# maintemp_revised_edition_2_20_18.net
KiCad netlist of a schematic drawn in EAGLE
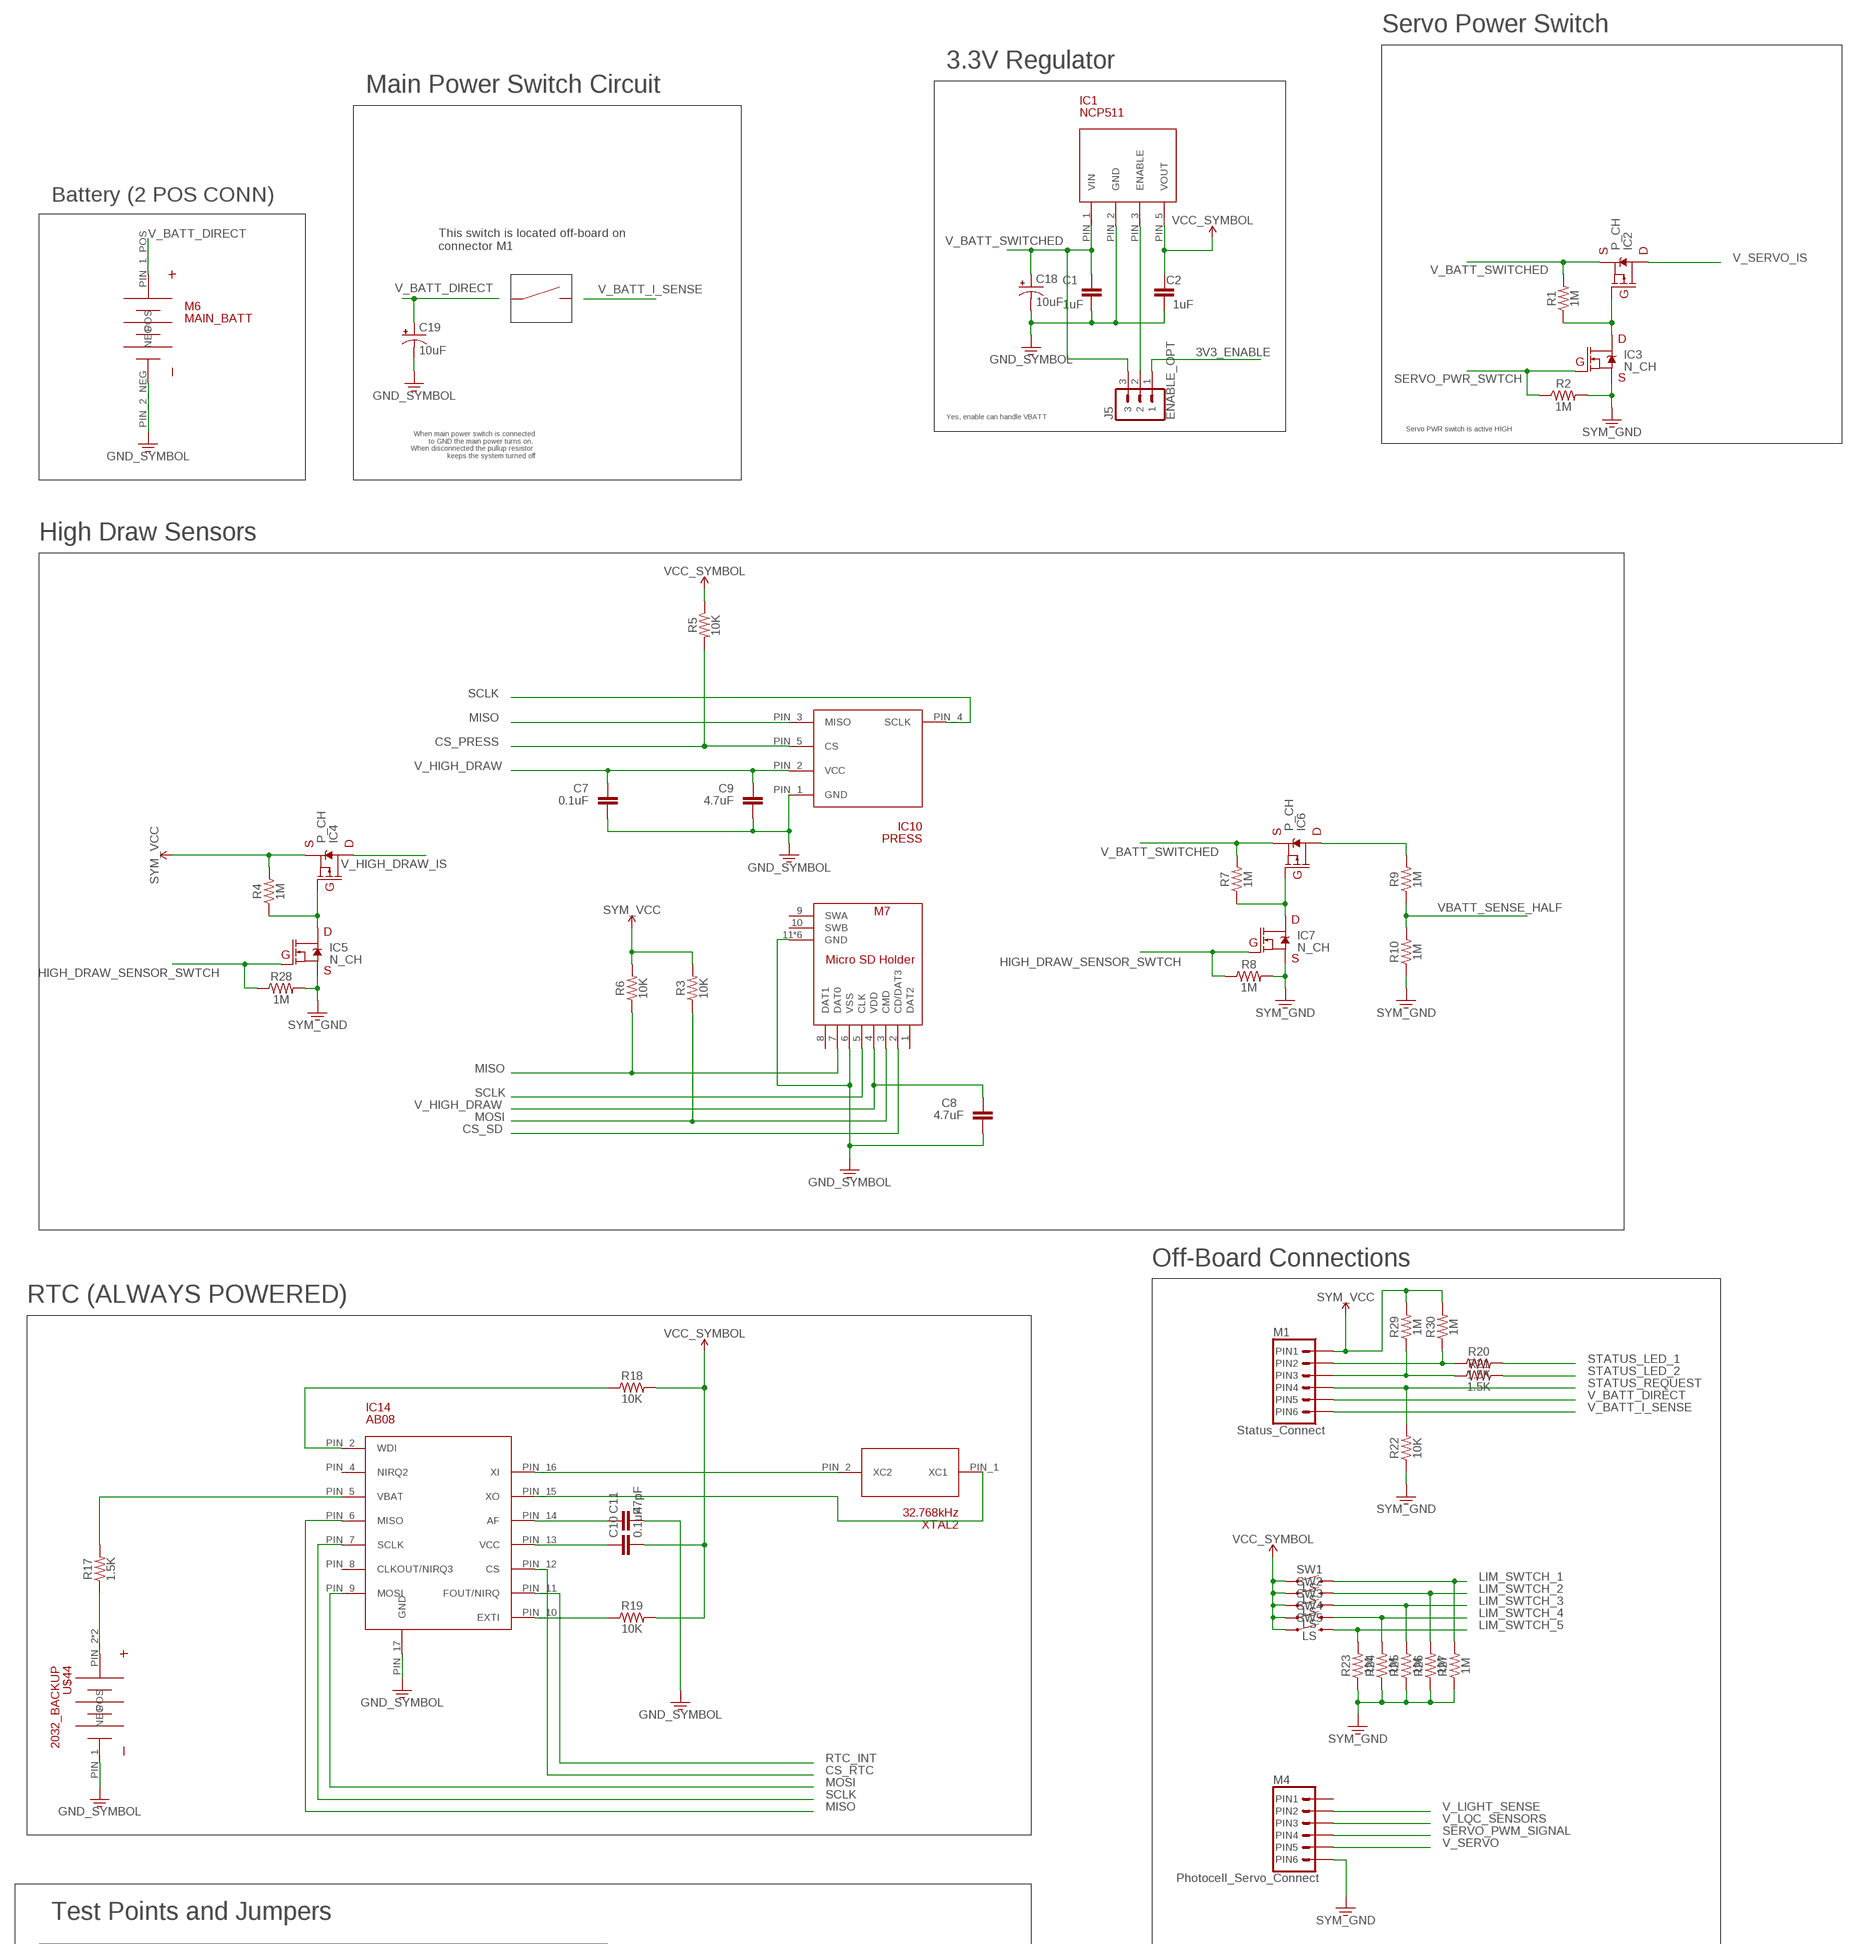
[diagram p0: schematic, sheet 1, part 1 of 3]
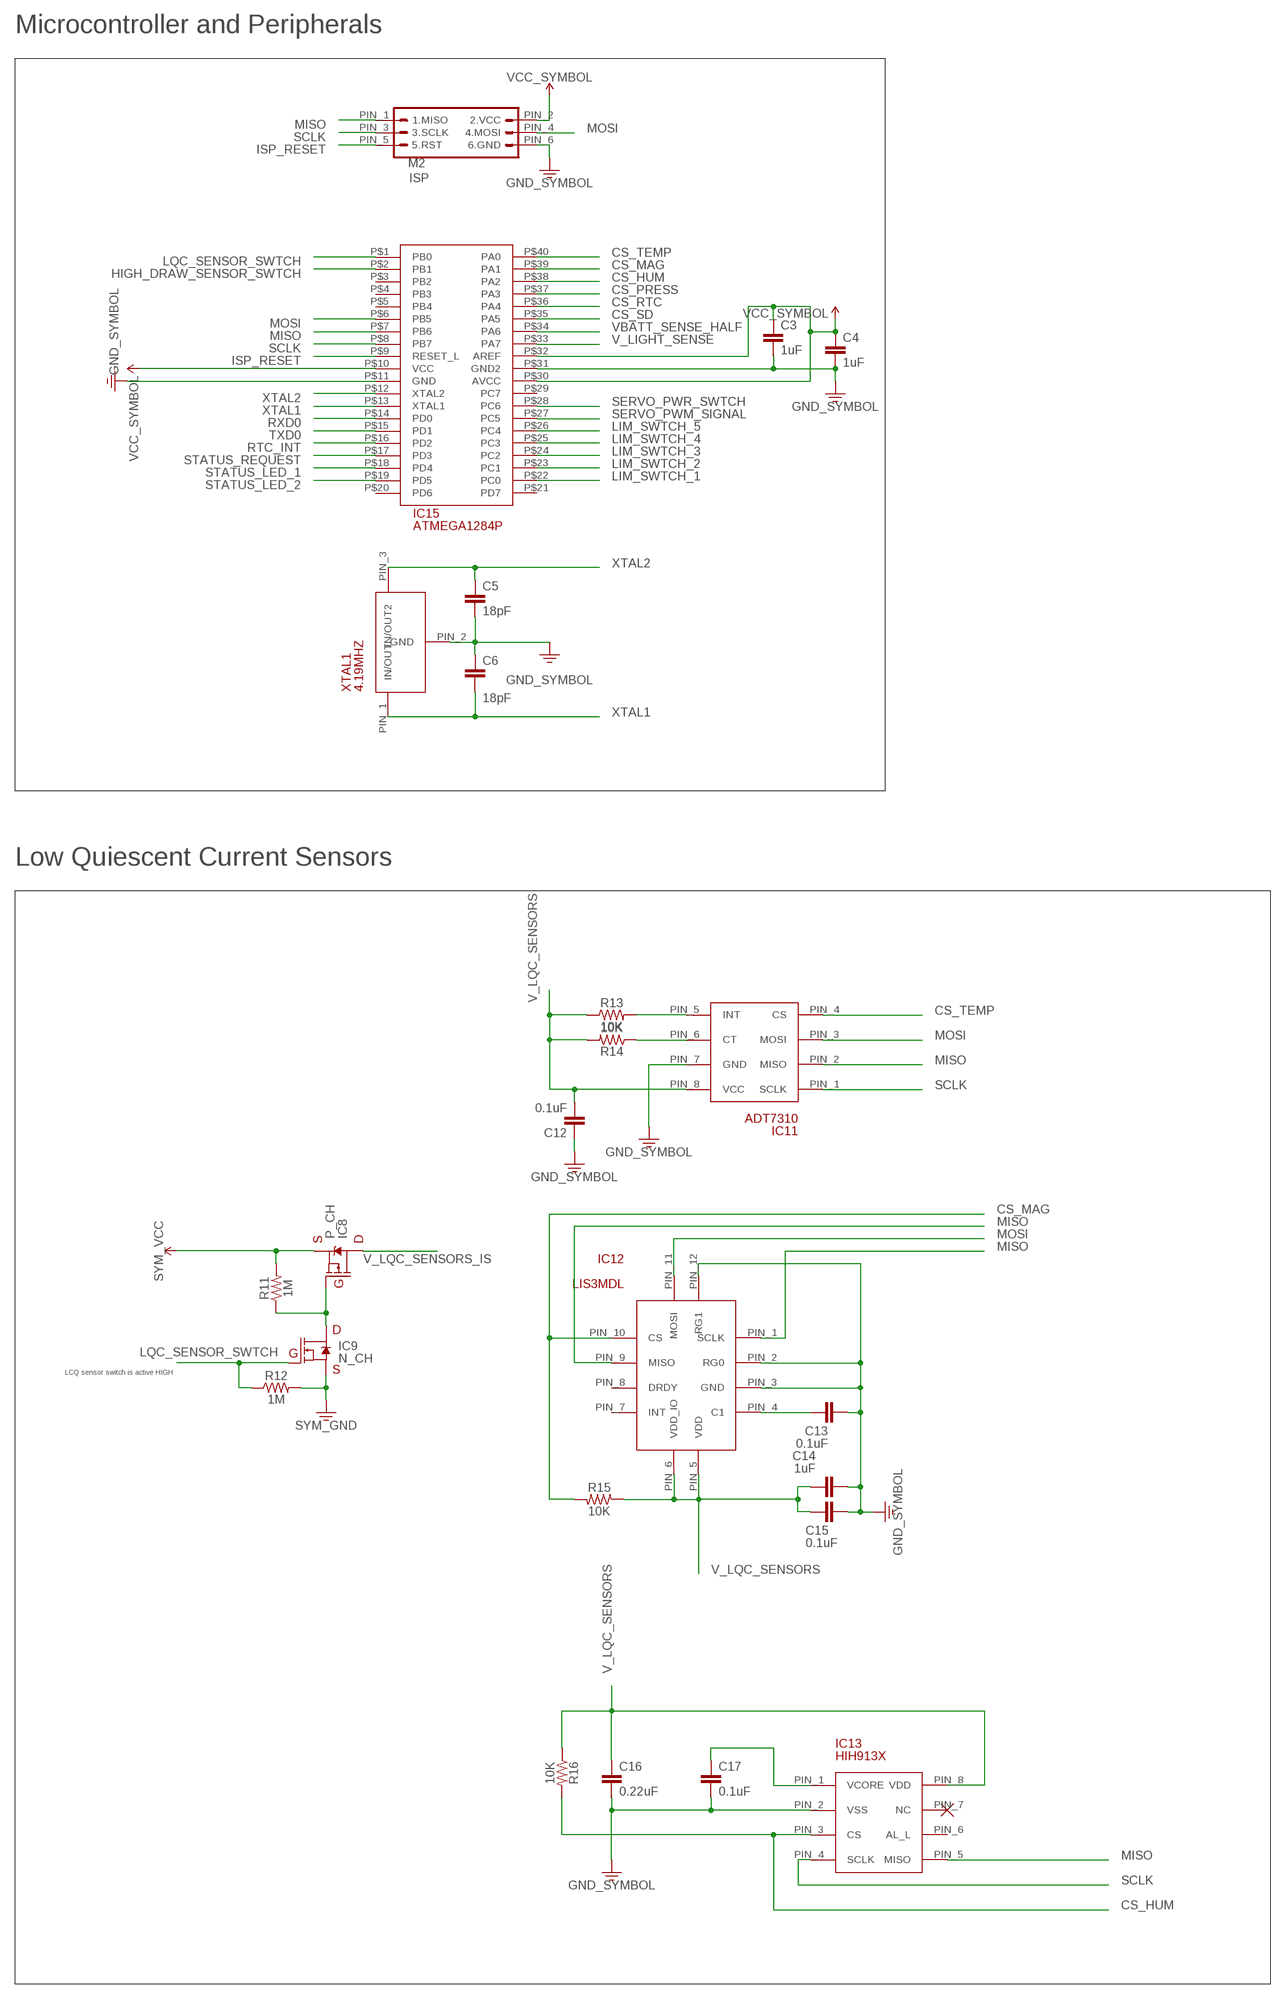
[diagram p1: schematic, sheet 1, part 2 of 3]
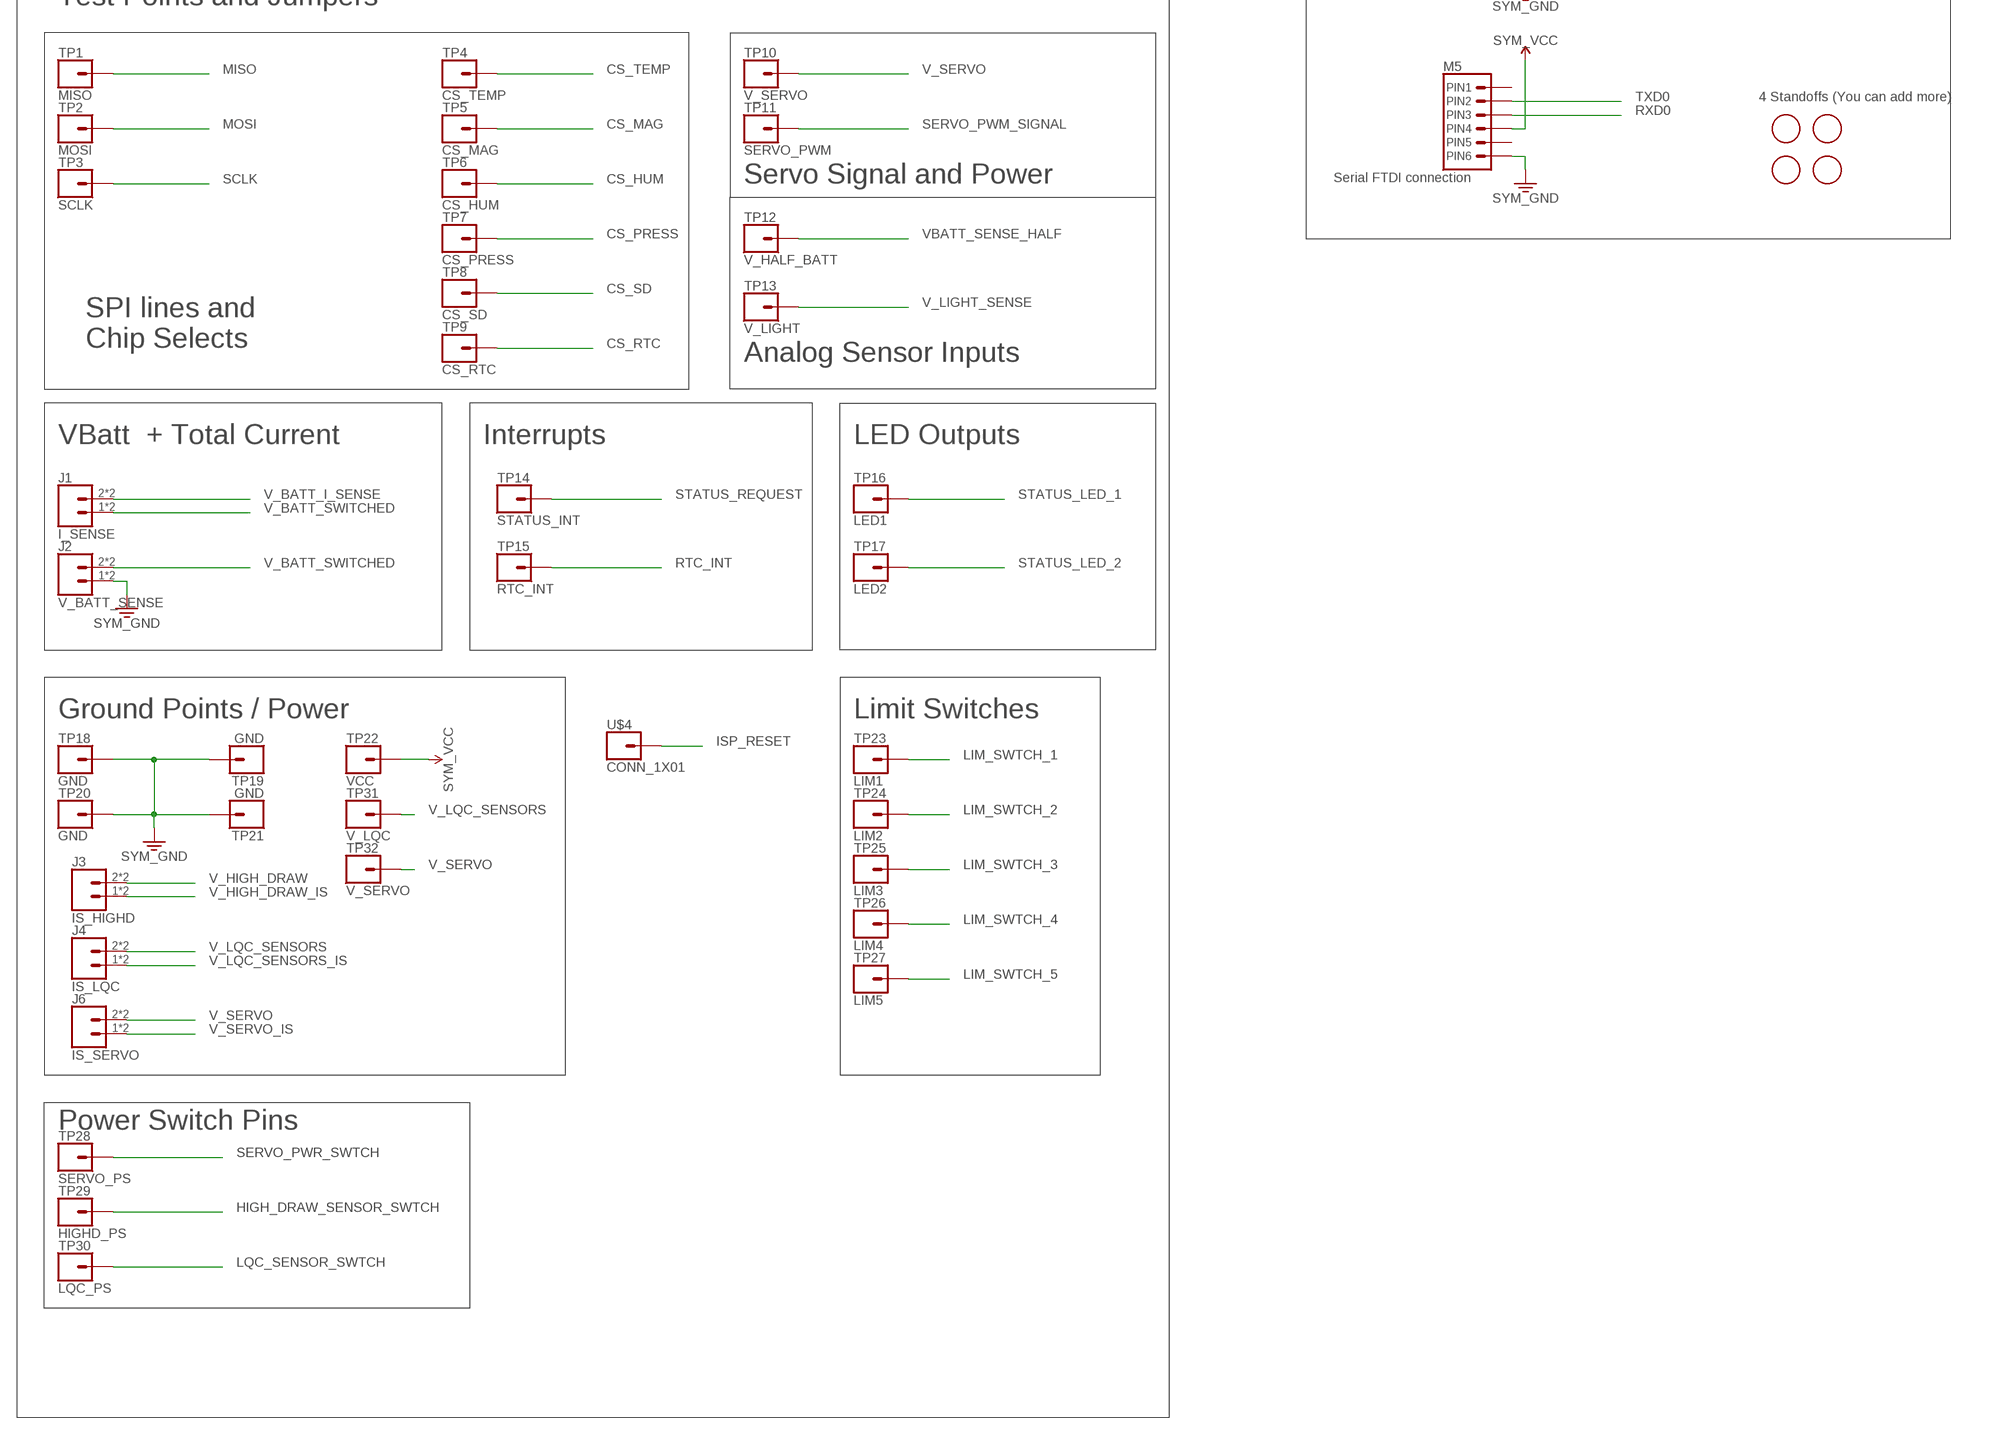
[diagram p2: schematic, sheet 1, part 3 of 3]

(export (version "E")
  (design (tool "Eeschema 10.0.6"))
  (components
    (comp (ref "C1")
      (value "1uF")
      (footprint "eagle-import:SMD_0603")
      (libsource (lib "eagle-import") (part "CAP_1UF"))
    )
    (comp (ref "C2")
      (value "1uF")
      (footprint "eagle-import:SMD_0603")
      (libsource (lib "eagle-import") (part "CAP_1UF"))
    )
    (comp (ref "C3")
      (value "1uF")
      (footprint "eagle-import:SMD_0603")
      (libsource (lib "eagle-import") (part "CAP_1UF"))
    )
    (comp (ref "C4")
      (value "1uF")
      (footprint "eagle-import:SMD_0603")
      (libsource (lib "eagle-import") (part "CAP_1UF"))
    )
    (comp (ref "C5")
      (value "18pF")
      (footprint "eagle-import:SMD_0603")
      (libsource (lib "eagle-import") (part "CAP_18PF"))
    )
    (comp (ref "C6")
      (value "18pF")
      (footprint "eagle-import:SMD_0603")
      (libsource (lib "eagle-import") (part "CAP_18PF"))
    )
    (comp (ref "C7")
      (value "0.1uF")
      (footprint "eagle-import:SMD_0603")
      (libsource (lib "eagle-import") (part "CAP_0.1UF"))
    )
    (comp (ref "C8")
      (value "4.7uF")
      (footprint "eagle-import:SMD_0603")
      (libsource (lib "eagle-import") (part "CAP_4.7UF"))
    )
    (comp (ref "C9")
      (value "4.7uF")
      (footprint "eagle-import:SMD_0603")
      (libsource (lib "eagle-import") (part "CAP_4.7UF"))
    )
    (comp (ref "C10")
      (value "0.1uF")
      (footprint "eagle-import:0603")
      (libsource (lib "eagle-import") (part "0.1UF_CAP"))
    )
    (comp (ref "C11")
      (value "47pF")
      (footprint "eagle-import:0603")
      (libsource (lib "eagle-import") (part "47PF_CAP"))
    )
    (comp (ref "C12")
      (value "0.1uF")
      (footprint "eagle-import:SMD_0603")
      (libsource (lib "eagle-import") (part "CAP_0.1UF"))
    )
    (comp (ref "C13")
      (value "0.1uF")
      (footprint "eagle-import:SMD_0603")
      (libsource (lib "eagle-import") (part "CAP_0.1UF"))
    )
    (comp (ref "C14")
      (value "1uF")
      (footprint "eagle-import:SMD_0603")
      (libsource (lib "eagle-import") (part "CAP_1UF"))
    )
    (comp (ref "C15")
      (value "0.1uF")
      (footprint "eagle-import:SMD_0603")
      (libsource (lib "eagle-import") (part "CAP_0.1UF"))
    )
    (comp (ref "C16")
      (value "0.22uF")
      (footprint "eagle-import:SMD_0603")
      (libsource (lib "eagle-import") (part "CAP_0.22UF"))
    )
    (comp (ref "C17")
      (value "0.1uF")
      (footprint "eagle-import:SMD_0603")
      (libsource (lib "eagle-import") (part "CAP_0.1UF"))
    )
    (comp (ref "C18")
      (value "10uF")
      (footprint "eagle-import:CAP-PTH-2.54")
      (libsource (lib "eagle-import") (part "CAP_ELECTRO"))
    )
    (comp (ref "C19")
      (value "10uF")
      (footprint "eagle-import:CAP-PTH-2.54")
      (libsource (lib "eagle-import") (part "CAP_ELECTRO"))
    )
    (comp (ref "IC1")
      (value "NCP511")
      (footprint "eagle-import:TSOP-5")
      (libsource (lib "eagle-import") (part "REG_NCP511"))
    )
    (comp (ref "IC2")
      (value "P_CH")
      (footprint "eagle-import:SOT23")
      (libsource (lib "eagle-import") (part "ZMISC_MOSFET_P_CHANNEL"))
    )
    (comp (ref "IC3")
      (value "N_CH")
      (footprint "eagle-import:SOT23")
      (libsource (lib "eagle-import") (part "ZMISC_MOSFET_N_CHANNEL"))
    )
    (comp (ref "IC4")
      (value "P_CH")
      (footprint "eagle-import:SOT23")
      (libsource (lib "eagle-import") (part "ZMISC_MOSFET_P_CHANNEL"))
    )
    (comp (ref "IC5")
      (value "N_CH")
      (footprint "eagle-import:SOT23")
      (libsource (lib "eagle-import") (part "ZMISC_MOSFET_N_CHANNEL"))
    )
    (comp (ref "IC6")
      (value "P_CH")
      (footprint "eagle-import:SOT23")
      (libsource (lib "eagle-import") (part "ZMISC_MOSFET_P_CHANNEL"))
    )
    (comp (ref "IC7")
      (value "N_CH")
      (footprint "eagle-import:SOT23")
      (libsource (lib "eagle-import") (part "ZMISC_MOSFET_N_CHANNEL"))
    )
    (comp (ref "IC8")
      (value "P_CH")
      (footprint "eagle-import:SOT23")
      (libsource (lib "eagle-import") (part "ZMISC_MOSFET_P_CHANNEL"))
    )
    (comp (ref "IC9")
      (value "N_CH")
      (footprint "eagle-import:SOT23")
      (libsource (lib "eagle-import") (part "ZMISC_MOSFET_N_CHANNEL"))
    )
    (comp (ref "IC10")
      (value "PRESS")
      (footprint "eagle-import:8-DIP")
      (libsource (lib "eagle-import") (part "SENS_PRESS_RSC"))
    )
    (comp (ref "IC11")
      (value "ADT7310")
      (footprint "eagle-import:SOIC-8")
      (libsource (lib "eagle-import") (part "TEMP_ADT7310"))
    )
    (comp (ref "IC12")
      (value "LIS3MDL")
      (footprint "eagle-import:LGA-12")
      (libsource (lib "eagle-import") (part "MAG_LIS3MDL"))
    )
    (comp (ref "IC13")
      (value "HIH913X")
      (footprint "eagle-import:SOIC-8")
      (libsource (lib "eagle-import") (part "HUM_HIH913X"))
    )
    (comp (ref "IC14")
      (value "AB08")
      (footprint "eagle-import:QFN16_3X3")
      (libsource (lib "eagle-import") (part "RTC_AB08"))
    )
    (comp (ref "IC15")
      (value "ATMEGA1284P")
      (footprint "eagle-import:40-DIP")
      (libsource (lib "eagle-import") (part "UC_ATMEGA1284P"))
    )
    (comp (ref "J1")
      (value "I_SENSE")
      (footprint "eagle-import:1X02")
      (libsource (lib "eagle-import") (part "ZMISC_JUMPER"))
    )
    (comp (ref "J2")
      (value "V_BATT_SENSE")
      (footprint "eagle-import:1X02")
      (libsource (lib "eagle-import") (part "ZMISC_JUMPER"))
    )
    (comp (ref "J3")
      (value "IS_HIGHD")
      (footprint "eagle-import:1X02")
      (libsource (lib "eagle-import") (part "ZMISC_JUMPER"))
    )
    (comp (ref "J4")
      (value "IS_LQC")
      (footprint "eagle-import:1X02")
      (libsource (lib "eagle-import") (part "ZMISC_JUMPER"))
    )
    (comp (ref "J5")
      (value "ENABLE_OPT")
      (footprint "eagle-import:1X03")
      (libsource (lib "eagle-import") (part "CONN_1X03"))
    )
    (comp (ref "J6")
      (value "IS_SERVO")
      (footprint "eagle-import:1X02")
      (libsource (lib "eagle-import") (part "ZMISC_JUMPER"))
    )
    (comp (ref "M1")
      (value "Status_Connect")
      (footprint "eagle-import:1X06")
      (libsource (lib "eagle-import") (part "CONN_SERIAL"))
    )
    (comp (ref "M2")
      (value "ISP")
      (footprint "eagle-import:2X3")
      (libsource (lib "eagle-import") (part "CONN_ISP"))
    )
    (comp (ref "M4")
      (value "Photocell_Servo_Connect")
      (footprint "eagle-import:1X06")
      (libsource (lib "eagle-import") (part "CONN_SERIAL"))
    )
    (comp (ref "M5")
      (value "Serial FTDI connection")
      (footprint "eagle-import:1X06")
      (libsource (lib "eagle-import") (part "CONN_SERIAL"))
    )
    (comp (ref "M6")
      (value "MAIN_BATT")
      (footprint "eagle-import:1-1318300-2")
      (libsource (lib "eagle-import") (part "PWR_MAIN_BATT"))
    )
    (comp (ref "M7")
      (value "SD")
      (footprint "eagle-import:MICRO-SD")
      (libsource (lib "eagle-import") (part "SENS_MICRO-SD"))
    )
    (comp (ref "R1")
      (value "1M")
      (footprint "eagle-import:SMD_0603")
      (libsource (lib "eagle-import") (part "RES_10K"))
    )
    (comp (ref "R2")
      (value "1M")
      (footprint "eagle-import:SMD_0603")
      (libsource (lib "eagle-import") (part "RES_10K"))
    )
    (comp (ref "R3")
      (value "10K")
      (footprint "eagle-import:SMD_0603")
      (libsource (lib "eagle-import") (part "RES_10K"))
    )
    (comp (ref "R4")
      (value "1M")
      (footprint "eagle-import:SMD_0603")
      (libsource (lib "eagle-import") (part "RES_10K"))
    )
    (comp (ref "R5")
      (value "10K")
      (footprint "eagle-import:SMD_0603")
      (libsource (lib "eagle-import") (part "RES_10K"))
    )
    (comp (ref "R6")
      (value "10K")
      (footprint "eagle-import:SMD_0603")
      (libsource (lib "eagle-import") (part "RES_10K"))
    )
    (comp (ref "R7")
      (value "1M")
      (footprint "eagle-import:SMD_0603")
      (libsource (lib "eagle-import") (part "RES_10K"))
    )
    (comp (ref "R8")
      (value "1M")
      (footprint "eagle-import:SMD_0603")
      (libsource (lib "eagle-import") (part "RES_10K"))
    )
    (comp (ref "R9")
      (value "1M")
      (footprint "eagle-import:SMD_0603")
      (libsource (lib "eagle-import") (part "RES_1M"))
    )
    (comp (ref "R10")
      (value "1M")
      (footprint "eagle-import:SMD_0603")
      (libsource (lib "eagle-import") (part "RES_1M"))
    )
    (comp (ref "R11")
      (value "1M")
      (footprint "eagle-import:SMD_0603")
      (libsource (lib "eagle-import") (part "RES_10K"))
    )
    (comp (ref "R12")
      (value "1M")
      (footprint "eagle-import:SMD_0603")
      (libsource (lib "eagle-import") (part "RES_10K"))
    )
    (comp (ref "R13")
      (value "10K")
      (footprint "eagle-import:SMD_0603")
      (libsource (lib "eagle-import") (part "RES_10K"))
    )
    (comp (ref "R14")
      (value "10K")
      (footprint "eagle-import:SMD_0603")
      (libsource (lib "eagle-import") (part "RES_10K"))
    )
    (comp (ref "R15")
      (value "10K")
      (footprint "eagle-import:SMD_0603")
      (libsource (lib "eagle-import") (part "RES_10K"))
    )
    (comp (ref "R16")
      (value "10K")
      (footprint "eagle-import:SMD_0603")
      (libsource (lib "eagle-import") (part "RES_10K"))
    )
    (comp (ref "R17")
      (value "1.5K")
      (footprint "eagle-import:0603")
      (libsource (lib "eagle-import") (part "1.5K_RES"))
    )
    (comp (ref "R18")
      (value "10K")
      (footprint "eagle-import:0603")
      (libsource (lib "eagle-import") (part "10K_RES"))
    )
    (comp (ref "R19")
      (value "10K")
      (footprint "eagle-import:0603")
      (libsource (lib "eagle-import") (part "10K_RES"))
    )
    (comp (ref "R20")
      (value "1.5K")
      (footprint "eagle-import:SMD_0603")
      (libsource (lib "eagle-import") (part "RES_1.5K"))
    )
    (comp (ref "R21")
      (value "1.5K")
      (footprint "eagle-import:SMD_0603")
      (libsource (lib "eagle-import") (part "RES_1.5K"))
    )
    (comp (ref "R22")
      (value "10K")
      (footprint "eagle-import:SMD_0603")
      (libsource (lib "eagle-import") (part "RES_10K"))
    )
    (comp (ref "R23")
      (value "1M")
      (footprint "eagle-import:SMD_0603")
      (libsource (lib "eagle-import") (part "RES_1M"))
    )
    (comp (ref "R24")
      (value "1M")
      (footprint "eagle-import:SMD_0603")
      (libsource (lib "eagle-import") (part "RES_1M"))
    )
    (comp (ref "R25")
      (value "1M")
      (footprint "eagle-import:SMD_0603")
      (libsource (lib "eagle-import") (part "RES_1M"))
    )
    (comp (ref "R26")
      (value "1M")
      (footprint "eagle-import:SMD_0603")
      (libsource (lib "eagle-import") (part "RES_1M"))
    )
    (comp (ref "R27")
      (value "1M")
      (footprint "eagle-import:SMD_0603")
      (libsource (lib "eagle-import") (part "RES_1M"))
    )
    (comp (ref "R28")
      (value "1M")
      (footprint "eagle-import:SMD_0603")
      (libsource (lib "eagle-import") (part "RES_10K"))
    )
    (comp (ref "R29")
      (value "1M")
      (footprint "eagle-import:SMD_0603")
      (libsource (lib "eagle-import") (part "RES_1M"))
    )
    (comp (ref "R30")
      (value "1M")
      (footprint "eagle-import:SMD_0603")
      (libsource (lib "eagle-import") (part "RES_1M"))
    )
    (comp (ref "SW1")
      (value "LS")
      (footprint "eagle-import:SNAPSWITCH")
      (libsource (lib "eagle-import") (part "LIMITSWITCHBASE"))
    )
    (comp (ref "SW2")
      (value "LS")
      (footprint "eagle-import:SNAPSWITCH")
      (libsource (lib "eagle-import") (part "LIMITSWITCHBASE"))
    )
    (comp (ref "SW3")
      (value "LS")
      (footprint "eagle-import:SNAPSWITCH")
      (libsource (lib "eagle-import") (part "LIMITSWITCHBASE"))
    )
    (comp (ref "SW4")
      (value "LS")
      (footprint "eagle-import:SNAPSWITCH")
      (libsource (lib "eagle-import") (part "LIMITSWITCHBASE"))
    )
    (comp (ref "SW5")
      (value "LS")
      (footprint "eagle-import:SNAPSWITCH")
      (libsource (lib "eagle-import") (part "LIMITSWITCHBASE"))
    )
    (comp (ref "TP1")
      (value "MISO")
      (footprint "eagle-import:1X01")
      (libsource (lib "eagle-import") (part "CONN_1X01"))
    )
    (comp (ref "TP2")
      (value "MOSI")
      (footprint "eagle-import:1X01")
      (libsource (lib "eagle-import") (part "CONN_1X01"))
    )
    (comp (ref "TP3")
      (value "SCLK")
      (footprint "eagle-import:1X01")
      (libsource (lib "eagle-import") (part "CONN_1X01"))
    )
    (comp (ref "TP4")
      (value "CS_TEMP")
      (footprint "eagle-import:1X01")
      (libsource (lib "eagle-import") (part "CONN_1X01"))
    )
    (comp (ref "TP5")
      (value "CS_MAG")
      (footprint "eagle-import:1X01")
      (libsource (lib "eagle-import") (part "CONN_1X01"))
    )
    (comp (ref "TP6")
      (value "CS_HUM")
      (footprint "eagle-import:1X01")
      (libsource (lib "eagle-import") (part "CONN_1X01"))
    )
    (comp (ref "TP7")
      (value "CS_PRESS")
      (footprint "eagle-import:1X01")
      (libsource (lib "eagle-import") (part "CONN_1X01"))
    )
    (comp (ref "TP8")
      (value "CS_SD")
      (footprint "eagle-import:1X01")
      (libsource (lib "eagle-import") (part "CONN_1X01"))
    )
    (comp (ref "TP9")
      (value "CS_RTC")
      (footprint "eagle-import:1X01")
      (libsource (lib "eagle-import") (part "CONN_1X01"))
    )
    (comp (ref "TP10")
      (value "V_SERVO")
      (footprint "eagle-import:1X01")
      (libsource (lib "eagle-import") (part "CONN_1X01"))
    )
    (comp (ref "TP11")
      (value "SERVO_PWM")
      (footprint "eagle-import:1X01")
      (libsource (lib "eagle-import") (part "CONN_1X01"))
    )
    (comp (ref "TP12")
      (value "V_HALF_BATT")
      (footprint "eagle-import:1X01")
      (libsource (lib "eagle-import") (part "CONN_1X01"))
    )
    (comp (ref "TP13")
      (value "V_LIGHT")
      (footprint "eagle-import:1X01")
      (libsource (lib "eagle-import") (part "CONN_1X01"))
    )
    (comp (ref "TP14")
      (value "STATUS_INT")
      (footprint "eagle-import:1X01")
      (libsource (lib "eagle-import") (part "CONN_1X01"))
    )
    (comp (ref "TP15")
      (value "RTC_INT")
      (footprint "eagle-import:1X01")
      (libsource (lib "eagle-import") (part "CONN_1X01"))
    )
    (comp (ref "TP16")
      (value "LED1")
      (footprint "eagle-import:1X01")
      (libsource (lib "eagle-import") (part "CONN_1X01"))
    )
    (comp (ref "TP17")
      (value "LED2")
      (footprint "eagle-import:1X01")
      (libsource (lib "eagle-import") (part "CONN_1X01"))
    )
    (comp (ref "TP18")
      (value "GND")
      (footprint "eagle-import:1X01")
      (libsource (lib "eagle-import") (part "CONN_1X01"))
    )
    (comp (ref "TP19")
      (value "GND")
      (footprint "eagle-import:1X01")
      (libsource (lib "eagle-import") (part "CONN_1X01"))
    )
    (comp (ref "TP20")
      (value "GND")
      (footprint "eagle-import:1X01")
      (libsource (lib "eagle-import") (part "CONN_1X01"))
    )
    (comp (ref "TP21")
      (value "GND")
      (footprint "eagle-import:1X01")
      (libsource (lib "eagle-import") (part "CONN_1X01"))
    )
    (comp (ref "TP22")
      (value "VCC")
      (footprint "eagle-import:1X01")
      (libsource (lib "eagle-import") (part "CONN_1X01"))
    )
    (comp (ref "TP23")
      (value "LIM1")
      (footprint "eagle-import:1X01")
      (libsource (lib "eagle-import") (part "CONN_1X01"))
    )
    (comp (ref "TP24")
      (value "LIM2")
      (footprint "eagle-import:1X01")
      (libsource (lib "eagle-import") (part "CONN_1X01"))
    )
    (comp (ref "TP25")
      (value "LIM3")
      (footprint "eagle-import:1X01")
      (libsource (lib "eagle-import") (part "CONN_1X01"))
    )
    (comp (ref "TP26")
      (value "LIM4")
      (footprint "eagle-import:1X01")
      (libsource (lib "eagle-import") (part "CONN_1X01"))
    )
    (comp (ref "TP27")
      (value "LIM5")
      (footprint "eagle-import:1X01")
      (libsource (lib "eagle-import") (part "CONN_1X01"))
    )
    (comp (ref "TP28")
      (value "SERVO_PS")
      (footprint "eagle-import:1X01")
      (libsource (lib "eagle-import") (part "CONN_1X01"))
    )
    (comp (ref "TP29")
      (value "HIGHD_PS")
      (footprint "eagle-import:1X01")
      (libsource (lib "eagle-import") (part "CONN_1X01"))
    )
    (comp (ref "TP30")
      (value "LQC_PS")
      (footprint "eagle-import:1X01")
      (libsource (lib "eagle-import") (part "CONN_1X01"))
    )
    (comp (ref "TP31")
      (value "V_LQC")
      (footprint "eagle-import:1X01")
      (libsource (lib "eagle-import") (part "CONN_1X01"))
    )
    (comp (ref "TP32")
      (value "V_SERVO")
      (footprint "eagle-import:1X01")
      (libsource (lib "eagle-import") (part "CONN_1X01"))
    )
    (comp (ref "U$4")
      (value "CONN_1X01")
      (footprint "eagle-import:1X01")
      (libsource (lib "eagle-import") (part "CONN_1X01"))
    )
    (comp (ref "U$7")
      (value "STANDOFF")
      (footprint "eagle-import:STANDOFF")
      (libsource (lib "eagle-import") (part "STANDOFF"))
    )
    (comp (ref "U$11")
      (value "STANDOFF")
      (footprint "eagle-import:STANDOFF")
      (libsource (lib "eagle-import") (part "STANDOFF"))
    )
    (comp (ref "U$13")
      (value "STANDOFF")
      (footprint "eagle-import:STANDOFF")
      (libsource (lib "eagle-import") (part "STANDOFF"))
    )
    (comp (ref "U$17")
      (value "STANDOFF")
      (footprint "eagle-import:STANDOFF")
      (libsource (lib "eagle-import") (part "STANDOFF"))
    )
    (comp (ref "U$44")
      (value "2032_BACKUP")
      (footprint "eagle-import:2032")
      (libsource (lib "eagle-import") (part "2032_BACKUP"))
    )
    (comp (ref "XTAL1")
      (value "4.19MHZ")
      (footprint "eagle-import:AT49")
      (libsource (lib "eagle-import") (part "ZMISC_XC"))
    )
    (comp (ref "XTAL2")
      (value "32.768kHz")
      (footprint "eagle-import:ABS07")
      (libsource (lib "eagle-import") (part "XC_RTC"))
    )
  )
  (nets
    (net (code "1") (name "/3V3_ENABLE") (class "Default")
      (node (ref "J5") (pin "1") (pinfunction "1_1") (pintype "passive"))
    )
    (net (code "2") (name "/CS_HUM") (class "Default")
      (node (ref "IC13") (pin "PIN_3") (pinfunction "CS_PIN_3") (pintype "bidirectional"))
      (node (ref "IC15") (pin "P$38") (pinfunction "PA2_P$38") (pintype "bidirectional"))
      (node (ref "R16") (pin "P$2") (pinfunction "2_P$2") (pintype "passive"))
      (node (ref "TP6") (pin "1") (pinfunction "1_1") (pintype "passive"))
    )
    (net (code "3") (name "/CS_MAG") (class "Default")
      (node (ref "IC12") (pin "PIN_10") (pinfunction "CS_PIN_10") (pintype "bidirectional"))
      (node (ref "IC15") (pin "P$39") (pinfunction "PA1_P$39") (pintype "bidirectional"))
      (node (ref "R15") (pin "P$2") (pinfunction "2_P$2") (pintype "passive"))
      (node (ref "TP5") (pin "1") (pinfunction "1_1") (pintype "passive"))
    )
    (net (code "4") (name "/CS_PRESS") (class "Default")
      (node (ref "IC10") (pin "PIN_5") (pinfunction "CS_PIN_5") (pintype "bidirectional"))
      (node (ref "IC15") (pin "P$37") (pinfunction "PA3_P$37") (pintype "bidirectional"))
      (node (ref "R5") (pin "P$2") (pinfunction "2_P$2") (pintype "passive"))
      (node (ref "TP7") (pin "1") (pinfunction "1_1") (pintype "passive"))
    )
    (net (code "5") (name "/CS_RTC") (class "Default")
      (node (ref "IC14") (pin "PIN_12") (pinfunction "CS_PIN_12") (pintype "bidirectional"))
      (node (ref "IC15") (pin "P$36") (pinfunction "PA4_P$36") (pintype "bidirectional"))
      (node (ref "TP9") (pin "1") (pinfunction "1_1") (pintype "passive"))
    )
    (net (code "6") (name "/CS_SD") (class "Default")
      (node (ref "IC15") (pin "P$35") (pinfunction "PA5_P$35") (pintype "bidirectional"))
      (node (ref "M7") (pin "2") (pinfunction "CD/DAT3_2") (pintype "bidirectional"))
      (node (ref "TP8") (pin "1") (pinfunction "1_1") (pintype "passive"))
    )
    (net (code "7") (name "/CS_TEMP") (class "Default")
      (node (ref "IC11") (pin "PIN_4") (pinfunction "CS_PIN_4") (pintype "bidirectional"))
      (node (ref "IC15") (pin "P$40") (pinfunction "PA0_P$40") (pintype "bidirectional"))
      (node (ref "TP4") (pin "1") (pinfunction "1_1") (pintype "passive"))
    )
    (net (code "8") (name "/HIGH_DRAW_SENSOR_SWTCH") (class "Default")
      (node (ref "IC15") (pin "P$2") (pinfunction "PB1_P$2") (pintype "bidirectional"))
      (node (ref "IC5") (pin "1") (pinfunction "G_1") (pintype "bidirectional"))
      (node (ref "IC7") (pin "1") (pinfunction "G_1") (pintype "bidirectional"))
      (node (ref "R28") (pin "P$1") (pinfunction "1_P$1") (pintype "passive"))
      (node (ref "R8") (pin "P$1") (pinfunction "1_P$1") (pintype "passive"))
      (node (ref "TP29") (pin "1") (pinfunction "1_1") (pintype "passive"))
    )
    (net (code "9") (name "/ISP_RESET") (class "Default")
      (node (ref "IC15") (pin "P$9") (pinfunction "RESET_L_P$9") (pintype "bidirectional"))
      (node (ref "M2") (pin "PIN_5") (pinfunction "5.RST_PIN_5") (pintype "bidirectional"))
      (node (ref "U$4") (pin "1") (pinfunction "1_1") (pintype "passive"))
    )
    (net (code "10") (name "/LIM_SWTCH_1") (class "Default")
      (node (ref "IC15") (pin "P$22") (pinfunction "PC0_P$22") (pintype "bidirectional"))
      (node (ref "R27") (pin "P$2") (pinfunction "2_P$2") (pintype "passive"))
      (node (ref "SW1") (pin "PIN_2") (pinfunction "2_PIN_2") (pintype "passive"))
      (node (ref "TP23") (pin "1") (pinfunction "1_1") (pintype "passive"))
    )
    (net (code "11") (name "/LIM_SWTCH_2") (class "Default")
      (node (ref "IC15") (pin "P$23") (pinfunction "PC1_P$23") (pintype "bidirectional"))
      (node (ref "R26") (pin "P$2") (pinfunction "2_P$2") (pintype "passive"))
      (node (ref "SW2") (pin "PIN_2") (pinfunction "2_PIN_2") (pintype "passive"))
      (node (ref "TP24") (pin "1") (pinfunction "1_1") (pintype "passive"))
    )
    (net (code "12") (name "/LIM_SWTCH_3") (class "Default")
      (node (ref "IC15") (pin "P$24") (pinfunction "PC2_P$24") (pintype "bidirectional"))
      (node (ref "R25") (pin "P$2") (pinfunction "2_P$2") (pintype "passive"))
      (node (ref "SW3") (pin "PIN_2") (pinfunction "2_PIN_2") (pintype "passive"))
      (node (ref "TP25") (pin "1") (pinfunction "1_1") (pintype "passive"))
    )
    (net (code "13") (name "/LIM_SWTCH_4") (class "Default")
      (node (ref "IC15") (pin "P$25") (pinfunction "PC3_P$25") (pintype "bidirectional"))
      (node (ref "R24") (pin "P$2") (pinfunction "2_P$2") (pintype "passive"))
      (node (ref "SW4") (pin "PIN_2") (pinfunction "2_PIN_2") (pintype "passive"))
      (node (ref "TP26") (pin "1") (pinfunction "1_1") (pintype "passive"))
    )
    (net (code "14") (name "/LIM_SWTCH_5") (class "Default")
      (node (ref "IC15") (pin "P$26") (pinfunction "PC4_P$26") (pintype "bidirectional"))
      (node (ref "R23") (pin "P$2") (pinfunction "2_P$2") (pintype "passive"))
      (node (ref "SW5") (pin "PIN_2") (pinfunction "2_PIN_2") (pintype "passive"))
      (node (ref "TP27") (pin "1") (pinfunction "1_1") (pintype "passive"))
    )
    (net (code "15") (name "/LQC_SENSOR_SWTCH") (class "Default")
      (node (ref "IC15") (pin "P$1") (pinfunction "PB0_P$1") (pintype "bidirectional"))
      (node (ref "IC9") (pin "1") (pinfunction "G_1") (pintype "bidirectional"))
      (node (ref "R12") (pin "P$1") (pinfunction "1_P$1") (pintype "passive"))
      (node (ref "TP30") (pin "1") (pinfunction "1_1") (pintype "passive"))
    )
    (net (code "16") (name "/MISO") (class "Default")
      (node (ref "IC10") (pin "PIN_3") (pinfunction "MISO_PIN_3") (pintype "bidirectional"))
      (node (ref "IC11") (pin "PIN_2") (pinfunction "MISO_PIN_2") (pintype "bidirectional"))
      (node (ref "IC12") (pin "PIN_1") (pinfunction "SCLK_PIN_1") (pintype "bidirectional"))
      (node (ref "IC12") (pin "PIN_9") (pinfunction "MISO_PIN_9") (pintype "bidirectional"))
      (node (ref "IC13") (pin "PIN_5") (pinfunction "MISO_PIN_5") (pintype "bidirectional"))
      (node (ref "IC14") (pin "PIN_6") (pinfunction "MISO_PIN_6") (pintype "bidirectional"))
      (node (ref "IC15") (pin "P$7") (pinfunction "PB6_P$7") (pintype "bidirectional"))
      (node (ref "M2") (pin "PIN_1") (pinfunction "1.MISO_PIN_1") (pintype "bidirectional"))
      (node (ref "M7") (pin "7") (pinfunction "DAT0_7") (pintype "bidirectional"))
      (node (ref "R6") (pin "P$1") (pinfunction "1_P$1") (pintype "passive"))
      (node (ref "TP1") (pin "1") (pinfunction "1_1") (pintype "passive"))
    )
    (net (code "17") (name "/MOSI") (class "Default")
      (node (ref "IC11") (pin "PIN_3") (pinfunction "MOSI_PIN_3") (pintype "bidirectional"))
      (node (ref "IC12") (pin "PIN_11") (pinfunction "MOSI_PIN_11") (pintype "bidirectional"))
      (node (ref "IC14") (pin "PIN_9") (pinfunction "MOSI_PIN_9") (pintype "bidirectional"))
      (node (ref "IC15") (pin "P$6") (pinfunction "PB5_P$6") (pintype "bidirectional"))
      (node (ref "M2") (pin "PIN_4") (pinfunction "4.MOSI_PIN_4") (pintype "bidirectional"))
      (node (ref "M7") (pin "3") (pinfunction "CMD_3") (pintype "bidirectional"))
      (node (ref "R3") (pin "P$1") (pinfunction "1_P$1") (pintype "passive"))
      (node (ref "TP2") (pin "1") (pinfunction "1_1") (pintype "passive"))
    )
    (net (code "18") (name "/RTC_INT") (class "Default")
      (node (ref "IC14") (pin "PIN_11") (pinfunction "FOUT/NIRQ_PIN_11") (pintype "bidirectional"))
      (node (ref "IC15") (pin "P$16") (pinfunction "PD2_P$16") (pintype "bidirectional"))
      (node (ref "TP15") (pin "1") (pinfunction "1_1") (pintype "passive"))
    )
    (net (code "19") (name "/RXD0") (class "Default")
      (node (ref "IC15") (pin "P$14") (pinfunction "PD0_P$14") (pintype "bidirectional"))
      (node (ref "M5") (pin "4") (pinfunction "PIN3_4") (pintype "passive"))
    )
    (net (code "20") (name "/SCLK") (class "Default")
      (node (ref "IC10") (pin "PIN_4") (pinfunction "SCLK_PIN_4") (pintype "bidirectional"))
      (node (ref "IC11") (pin "PIN_1") (pinfunction "SCLK_PIN_1") (pintype "bidirectional"))
      (node (ref "IC13") (pin "PIN_4") (pinfunction "SCLK_PIN_4") (pintype "bidirectional"))
      (node (ref "IC14") (pin "PIN_7") (pinfunction "SCLK_PIN_7") (pintype "bidirectional"))
      (node (ref "IC15") (pin "P$8") (pinfunction "PB7_P$8") (pintype "bidirectional"))
      (node (ref "M2") (pin "PIN_3") (pinfunction "3.SCLK_PIN_3") (pintype "bidirectional"))
      (node (ref "M7") (pin "5") (pinfunction "CLK_5") (pintype "bidirectional"))
      (node (ref "TP3") (pin "1") (pinfunction "1_1") (pintype "passive"))
    )
    (net (code "21") (name "/SERVO_PWM_SIGNAL") (class "Default")
      (node (ref "IC15") (pin "P$27") (pinfunction "PC5_P$27") (pintype "bidirectional"))
      (node (ref "M4") (pin "3") (pinfunction "PIN4_3") (pintype "passive"))
      (node (ref "TP11") (pin "1") (pinfunction "1_1") (pintype "passive"))
    )
    (net (code "22") (name "/SERVO_PWR_SWTCH") (class "Default")
      (node (ref "IC15") (pin "P$28") (pinfunction "PC6_P$28") (pintype "bidirectional"))
      (node (ref "IC3") (pin "1") (pinfunction "G_1") (pintype "bidirectional"))
      (node (ref "R2") (pin "P$1") (pinfunction "1_P$1") (pintype "passive"))
      (node (ref "TP28") (pin "1") (pinfunction "1_1") (pintype "passive"))
    )
    (net (code "23") (name "/STATUS_LED_1") (class "Default")
      (node (ref "IC15") (pin "P$18") (pinfunction "PD4_P$18") (pintype "bidirectional"))
      (node (ref "R20") (pin "P$2") (pinfunction "2_P$2") (pintype "passive"))
      (node (ref "TP16") (pin "1") (pinfunction "1_1") (pintype "passive"))
    )
    (net (code "24") (name "/STATUS_LED_2") (class "Default")
      (node (ref "IC15") (pin "P$19") (pinfunction "PD5_P$19") (pintype "bidirectional"))
      (node (ref "R21") (pin "P$2") (pinfunction "2_P$2") (pintype "passive"))
      (node (ref "TP17") (pin "1") (pinfunction "1_1") (pintype "passive"))
    )
    (net (code "25") (name "/STATUS_REQUEST") (class "Default")
      (node (ref "IC15") (pin "P$17") (pinfunction "PD3_P$17") (pintype "bidirectional"))
      (node (ref "M1") (pin "3") (pinfunction "PIN4_3") (pintype "passive"))
      (node (ref "R22") (pin "P$2") (pinfunction "2_P$2") (pintype "passive"))
      (node (ref "TP14") (pin "1") (pinfunction "1_1") (pintype "passive"))
    )
    (net (code "26") (name "/TXD0") (class "Default")
      (node (ref "IC15") (pin "P$15") (pinfunction "PD1_P$15") (pintype "bidirectional"))
      (node (ref "M5") (pin "5") (pinfunction "PIN2_5") (pintype "passive"))
    )
    (net (code "27") (name "/VBATT_SENSE_HALF") (class "Default")
      (node (ref "IC15") (pin "P$34") (pinfunction "PA6_P$34") (pintype "bidirectional"))
      (node (ref "R10") (pin "P$2") (pinfunction "2_P$2") (pintype "passive"))
      (node (ref "R9") (pin "P$1") (pinfunction "1_P$1") (pintype "passive"))
      (node (ref "TP12") (pin "1") (pinfunction "1_1") (pintype "passive"))
    )
    (net (code "28") (name "/V_BATT_DIRECT") (class "Default")
      (node (ref "C19") (pin "1") (pinfunction "+_1") (pintype "passive"))
      (node (ref "M1") (pin "2") (pinfunction "PIN5_2") (pintype "passive"))
      (node (ref "M6") (pin "PIN_1_POS") (pinfunction "POS_PIN_1_POS") (pintype "bidirectional"))
    )
    (net (code "29") (name "/V_BATT_I_SENSE") (class "Default")
      (node (ref "J1") (pin "2") (pinfunction "2_2") (pintype "passive"))
      (node (ref "J1") (pin "P$2") (pinfunction "2_P$2") (pintype "passive"))
      (node (ref "M1") (pin "1") (pinfunction "PIN6_1") (pintype "passive"))
    )
    (net (code "30") (name "/V_BATT_SWITCHED") (class "Default")
      (node (ref "C1") (pin "P$1") (pinfunction "1_P$1") (pintype "passive"))
      (node (ref "C18") (pin "1") (pinfunction "+_1") (pintype "passive"))
      (node (ref "IC1") (pin "PIN_1") (pinfunction "VIN_PIN_1") (pintype "bidirectional"))
      (node (ref "IC2") (pin "2") (pinfunction "S_2") (pintype "bidirectional"))
      (node (ref "IC6") (pin "2") (pinfunction "S_2") (pintype "bidirectional"))
      (node (ref "J1") (pin "1") (pinfunction "1_1") (pintype "passive"))
      (node (ref "J1") (pin "P$1") (pinfunction "1_P$1") (pintype "passive"))
      (node (ref "J2") (pin "2") (pinfunction "2_2") (pintype "passive"))
      (node (ref "J2") (pin "P$2") (pinfunction "2_P$2") (pintype "passive"))
      (node (ref "J5") (pin "3") (pinfunction "3_3") (pintype "passive"))
      (node (ref "R1") (pin "P$2") (pinfunction "2_P$2") (pintype "passive"))
      (node (ref "R7") (pin "P$2") (pinfunction "2_P$2") (pintype "passive"))
    )
    (net (code "31") (name "/V_HIGH_DRAW") (class "Default")
      (node (ref "C7") (pin "P$1") (pinfunction "1_P$1") (pintype "passive"))
      (node (ref "C8") (pin "P$2") (pinfunction "2_P$2") (pintype "passive"))
      (node (ref "C9") (pin "P$1") (pinfunction "1_P$1") (pintype "passive"))
      (node (ref "IC10") (pin "PIN_2") (pinfunction "VCC_PIN_2") (pintype "bidirectional"))
      (node (ref "J3") (pin "2") (pinfunction "2_2") (pintype "passive"))
      (node (ref "J3") (pin "P$2") (pinfunction "2_P$2") (pintype "passive"))
      (node (ref "M7") (pin "4") (pinfunction "VDD_4") (pintype "bidirectional"))
    )
    (net (code "32") (name "/V_HIGH_DRAW_IS") (class "Default")
      (node (ref "IC4") (pin "3") (pinfunction "D_3") (pintype "bidirectional"))
      (node (ref "J3") (pin "1") (pinfunction "1_1") (pintype "passive"))
      (node (ref "J3") (pin "P$1") (pinfunction "1_P$1") (pintype "passive"))
    )
    (net (code "33") (name "/V_LIGHT_SENSE") (class "Default")
      (node (ref "IC15") (pin "P$33") (pinfunction "PA7_P$33") (pintype "bidirectional"))
      (node (ref "M4") (pin "5") (pinfunction "PIN2_5") (pintype "passive"))
      (node (ref "TP13") (pin "1") (pinfunction "1_1") (pintype "passive"))
    )
    (net (code "34") (name "/V_LQC_SENSORS") (class "Default")
      (node (ref "C12") (pin "P$2") (pinfunction "2_P$2") (pintype "passive"))
      (node (ref "C14") (pin "P$2") (pinfunction "2_P$2") (pintype "passive"))
      (node (ref "C15") (pin "P$1") (pinfunction "1_P$1") (pintype "passive"))
      (node (ref "C16") (pin "P$1") (pinfunction "1_P$1") (pintype "passive"))
      (node (ref "IC11") (pin "PIN_8") (pinfunction "VCC_PIN_8") (pintype "bidirectional"))
      (node (ref "IC12") (pin "PIN_5") (pinfunction "VDD_PIN_5") (pintype "bidirectional"))
      (node (ref "IC12") (pin "PIN_6") (pinfunction "VDD_IO_PIN_6") (pintype "bidirectional"))
      (node (ref "IC13") (pin "PIN_8") (pinfunction "VDD_PIN_8") (pintype "bidirectional"))
      (node (ref "J4") (pin "2") (pinfunction "2_2") (pintype "passive"))
      (node (ref "J4") (pin "P$2") (pinfunction "2_P$2") (pintype "passive"))
      (node (ref "M4") (pin "4") (pinfunction "PIN3_4") (pintype "passive"))
      (node (ref "R13") (pin "P$1") (pinfunction "1_P$1") (pintype "passive"))
      (node (ref "R14") (pin "P$2") (pinfunction "2_P$2") (pintype "passive"))
      (node (ref "R15") (pin "P$1") (pinfunction "1_P$1") (pintype "passive"))
      (node (ref "R16") (pin "P$1") (pinfunction "1_P$1") (pintype "passive"))
      (node (ref "TP31") (pin "1") (pinfunction "1_1") (pintype "passive"))
    )
    (net (code "35") (name "/V_LQC_SENSORS_IS") (class "Default")
      (node (ref "IC8") (pin "3") (pinfunction "D_3") (pintype "bidirectional"))
      (node (ref "J4") (pin "1") (pinfunction "1_1") (pintype "passive"))
      (node (ref "J4") (pin "P$1") (pinfunction "1_P$1") (pintype "passive"))
    )
    (net (code "36") (name "/V_SERVO") (class "Default")
      (node (ref "J6") (pin "2") (pinfunction "2_2") (pintype "passive"))
      (node (ref "J6") (pin "P$2") (pinfunction "2_P$2") (pintype "passive"))
      (node (ref "M4") (pin "2") (pinfunction "PIN5_2") (pintype "passive"))
      (node (ref "TP10") (pin "1") (pinfunction "1_1") (pintype "passive"))
      (node (ref "TP32") (pin "1") (pinfunction "1_1") (pintype "passive"))
    )
    (net (code "37") (name "/V_SERVO_IS") (class "Default")
      (node (ref "IC2") (pin "3") (pinfunction "D_3") (pintype "bidirectional"))
      (node (ref "J6") (pin "1") (pinfunction "1_1") (pintype "passive"))
      (node (ref "J6") (pin "P$1") (pinfunction "1_P$1") (pintype "passive"))
    )
    (net (code "38") (name "/XTAL1") (class "Default")
      (node (ref "C6") (pin "P$2") (pinfunction "2_P$2") (pintype "passive"))
      (node (ref "IC15") (pin "P$13") (pinfunction "XTAL1_P$13") (pintype "bidirectional"))
      (node (ref "XTAL1") (pin "PIN_1") (pinfunction "IN/OUT_PIN_1") (pintype "bidirectional"))
    )
    (net (code "39") (name "/XTAL2") (class "Default")
      (node (ref "C5") (pin "P$1") (pinfunction "1_P$1") (pintype "passive"))
      (node (ref "IC15") (pin "P$12") (pinfunction "XTAL2_P$12") (pintype "bidirectional"))
      (node (ref "XTAL1") (pin "PIN_3") (pinfunction "IN/OUT2_PIN_3") (pintype "bidirectional"))
    )
    (net (code "40") (name "GND_SYMBOL") (class "Default")
      (node (ref "C1") (pin "P$2") (pinfunction "2_P$2") (pintype "passive"))
      (node (ref "C11") (pin "2") (pinfunction "2_2") (pintype "passive"))
      (node (ref "C12") (pin "P$1") (pinfunction "1_P$1") (pintype "passive"))
      (node (ref "C13") (pin "P$1") (pinfunction "1_P$1") (pintype "passive"))
      (node (ref "C14") (pin "P$1") (pinfunction "1_P$1") (pintype "passive"))
      (node (ref "C15") (pin "P$2") (pinfunction "2_P$2") (pintype "passive"))
      (node (ref "C16") (pin "P$2") (pinfunction "2_P$2") (pintype "passive"))
      (node (ref "C17") (pin "P$2") (pinfunction "2_P$2") (pintype "passive"))
      (node (ref "C18") (pin "2") (pinfunction "-_2") (pintype "passive"))
      (node (ref "C19") (pin "2") (pinfunction "-_2") (pintype "passive"))
      (node (ref "C2") (pin "P$1") (pinfunction "1_P$1") (pintype "passive"))
      (node (ref "C3") (pin "P$2") (pinfunction "2_P$2") (pintype "passive"))
      (node (ref "C4") (pin "P$2") (pinfunction "2_P$2") (pintype "passive"))
      (node (ref "C5") (pin "P$2") (pinfunction "2_P$2") (pintype "passive"))
      (node (ref "C6") (pin "P$1") (pinfunction "1_P$1") (pintype "passive"))
      (node (ref "C7") (pin "P$2") (pinfunction "2_P$2") (pintype "passive"))
      (node (ref "C8") (pin "P$1") (pinfunction "1_P$1") (pintype "passive"))
      (node (ref "C9") (pin "P$2") (pinfunction "2_P$2") (pintype "passive"))
      (node (ref "IC1") (pin "PIN_2") (pinfunction "GND_PIN_2") (pintype "bidirectional"))
      (node (ref "IC10") (pin "PIN_1") (pinfunction "GND_PIN_1") (pintype "bidirectional"))
      (node (ref "IC11") (pin "PIN_7") (pinfunction "GND_PIN_7") (pintype "bidirectional"))
      (node (ref "IC12") (pin "PIN_12") (pinfunction "RG1_PIN_12") (pintype "bidirectional"))
      (node (ref "IC12") (pin "PIN_2") (pinfunction "RG0_PIN_2") (pintype "bidirectional"))
      (node (ref "IC12") (pin "PIN_3") (pinfunction "GND_PIN_3") (pintype "bidirectional"))
      (node (ref "IC13") (pin "PIN_2") (pinfunction "VSS_PIN_2") (pintype "bidirectional"))
      (node (ref "IC14") (pin "PIN_17") (pinfunction "GND_PIN_17") (pintype "bidirectional"))
      (node (ref "IC15") (pin "P$11") (pinfunction "GND_P$11") (pintype "bidirectional"))
      (node (ref "IC15") (pin "P$31") (pinfunction "GND2_P$31") (pintype "bidirectional"))
      (node (ref "IC3") (pin "2") (pinfunction "S_2") (pintype "bidirectional"))
      (node (ref "IC5") (pin "2") (pinfunction "S_2") (pintype "bidirectional"))
      (node (ref "IC7") (pin "2") (pinfunction "S_2") (pintype "bidirectional"))
      (node (ref "IC9") (pin "2") (pinfunction "S_2") (pintype "bidirectional"))
      (node (ref "J2") (pin "1") (pinfunction "1_1") (pintype "passive"))
      (node (ref "J2") (pin "P$1") (pinfunction "1_P$1") (pintype "passive"))
      (node (ref "M2") (pin "PIN_6") (pinfunction "6.GND_PIN_6") (pintype "bidirectional"))
      (node (ref "M4") (pin "1") (pinfunction "PIN6_1") (pintype "passive"))
      (node (ref "M5") (pin "1") (pinfunction "PIN6_1") (pintype "passive"))
      (node (ref "M6") (pin "PIN_2_NEG") (pinfunction "NEG_PIN_2_NEG") (pintype "bidirectional"))
      (node (ref "M7") (pin "11") (pinfunction "GND_11") (pintype "bidirectional"))
      (node (ref "M7") (pin "12") (pinfunction "GND_12") (pintype "bidirectional"))
      (node (ref "M7") (pin "13") (pinfunction "GND_13") (pintype "bidirectional"))
      (node (ref "M7") (pin "14") (pinfunction "GND_14") (pintype "bidirectional"))
      (node (ref "M7") (pin "15") (pinfunction "GND_15") (pintype "bidirectional"))
      (node (ref "M7") (pin "16") (pinfunction "GND_16") (pintype "bidirectional"))
      (node (ref "M7") (pin "6") (pinfunction "VSS_6") (pintype "bidirectional"))
      (node (ref "R10") (pin "P$1") (pinfunction "1_P$1") (pintype "passive"))
      (node (ref "R12") (pin "P$2") (pinfunction "2_P$2") (pintype "passive"))
      (node (ref "R2") (pin "P$2") (pinfunction "2_P$2") (pintype "passive"))
      (node (ref "R22") (pin "P$1") (pinfunction "1_P$1") (pintype "passive"))
      (node (ref "R23") (pin "P$1") (pinfunction "1_P$1") (pintype "passive"))
      (node (ref "R24") (pin "P$1") (pinfunction "1_P$1") (pintype "passive"))
      (node (ref "R25") (pin "P$1") (pinfunction "1_P$1") (pintype "passive"))
      (node (ref "R26") (pin "P$1") (pinfunction "1_P$1") (pintype "passive"))
      (node (ref "R27") (pin "P$1") (pinfunction "1_P$1") (pintype "passive"))
      (node (ref "R28") (pin "P$2") (pinfunction "2_P$2") (pintype "passive"))
      (node (ref "R8") (pin "P$2") (pinfunction "2_P$2") (pintype "passive"))
      (node (ref "TP18") (pin "1") (pinfunction "1_1") (pintype "passive"))
      (node (ref "TP19") (pin "1") (pinfunction "1_1") (pintype "passive"))
      (node (ref "TP20") (pin "1") (pinfunction "1_1") (pintype "passive"))
      (node (ref "TP21") (pin "1") (pinfunction "1_1") (pintype "passive"))
      (node (ref "U$44") (pin "PIN_1") (pinfunction "NEG_PIN_1") (pintype "bidirectional"))
      (node (ref "XTAL1") (pin "PIN_2") (pinfunction "GND_PIN_2") (pintype "bidirectional"))
    )
    (net (code "41") (name "Net-(C13-2)") (class "Default")
      (node (ref "C13") (pin "P$2") (pinfunction "2_P$2") (pintype "passive"))
      (node (ref "IC12") (pin "PIN_4") (pinfunction "C1_PIN_4") (pintype "bidirectional"))
    )
    (net (code "42") (name "Net-(C17-1)") (class "Default")
      (node (ref "C17") (pin "P$1") (pinfunction "1_P$1") (pintype "passive"))
      (node (ref "IC13") (pin "PIN_1") (pinfunction "VCORE_PIN_1") (pintype "bidirectional"))
    )
    (net (code "43") (name "Net-(IC1-ENABLE)") (class "Default")
      (node (ref "IC1") (pin "PIN_3") (pinfunction "ENABLE_PIN_3") (pintype "bidirectional"))
      (node (ref "J5") (pin "2") (pinfunction "2_2") (pintype "passive"))
    )
    (net (code "44") (name "Net-(IC2-G)") (class "Default")
      (node (ref "IC2") (pin "1") (pinfunction "G_1") (pintype "bidirectional"))
      (node (ref "IC3") (pin "3") (pinfunction "D_3") (pintype "bidirectional"))
      (node (ref "R1") (pin "P$1") (pinfunction "1_P$1") (pintype "passive"))
    )
    (net (code "45") (name "Net-(IC4-G)") (class "Default")
      (node (ref "IC4") (pin "1") (pinfunction "G_1") (pintype "bidirectional"))
      (node (ref "IC5") (pin "3") (pinfunction "D_3") (pintype "bidirectional"))
      (node (ref "R4") (pin "P$1") (pinfunction "1_P$1") (pintype "passive"))
    )
    (net (code "46") (name "Net-(IC6-D)") (class "Default")
      (node (ref "IC6") (pin "3") (pinfunction "D_3") (pintype "bidirectional"))
      (node (ref "R9") (pin "P$2") (pinfunction "2_P$2") (pintype "passive"))
    )
    (net (code "47") (name "Net-(IC6-G)") (class "Default")
      (node (ref "IC6") (pin "1") (pinfunction "G_1") (pintype "bidirectional"))
      (node (ref "IC7") (pin "3") (pinfunction "D_3") (pintype "bidirectional"))
      (node (ref "R7") (pin "P$1") (pinfunction "1_P$1") (pintype "passive"))
    )
    (net (code "48") (name "Net-(IC8-G)") (class "Default")
      (node (ref "IC8") (pin "1") (pinfunction "G_1") (pintype "bidirectional"))
      (node (ref "IC9") (pin "3") (pinfunction "D_3") (pintype "bidirectional"))
      (node (ref "R11") (pin "P$1") (pinfunction "1_P$1") (pintype "passive"))
    )
    (net (code "49") (name "Net-(IC11-CT)") (class "Default")
      (node (ref "IC11") (pin "PIN_6") (pinfunction "CT_PIN_6") (pintype "bidirectional"))
      (node (ref "R14") (pin "P$1") (pinfunction "1_P$1") (pintype "passive"))
    )
    (net (code "50") (name "Net-(IC11-INT)") (class "Default")
      (node (ref "IC11") (pin "PIN_5") (pinfunction "INT_PIN_5") (pintype "bidirectional"))
      (node (ref "R13") (pin "P$2") (pinfunction "2_P$2") (pintype "passive"))
    )
    (net (code "51") (name "Net-(IC14-AF)") (class "Default")
      (node (ref "C11") (pin "1") (pinfunction "1_1") (pintype "passive"))
      (node (ref "IC14") (pin "PIN_14") (pinfunction "AF_PIN_14") (pintype "bidirectional"))
    )
    (net (code "52") (name "Net-(IC14-EXTI)") (class "Default")
      (node (ref "IC14") (pin "PIN_10") (pinfunction "EXTI_PIN_10") (pintype "bidirectional"))
      (node (ref "R19") (pin "1") (pinfunction "1_1") (pintype "passive"))
    )
    (net (code "53") (name "Net-(IC14-VBAT)") (class "Default")
      (node (ref "IC14") (pin "PIN_5") (pinfunction "VBAT_PIN_5") (pintype "bidirectional"))
      (node (ref "R17") (pin "2") (pinfunction "2_2") (pintype "passive"))
    )
    (net (code "54") (name "Net-(IC14-VCC)") (class "Default")
      (node (ref "C10") (pin "1") (pinfunction "1_1") (pintype "passive"))
      (node (ref "IC14") (pin "PIN_13") (pinfunction "VCC_PIN_13") (pintype "bidirectional"))
    )
    (net (code "55") (name "Net-(IC14-WDI)") (class "Default")
      (node (ref "IC14") (pin "PIN_2") (pinfunction "WDI_PIN_2") (pintype "bidirectional"))
      (node (ref "R18") (pin "1") (pinfunction "1_1") (pintype "passive"))
    )
    (net (code "56") (name "Net-(IC14-XI)") (class "Default")
      (node (ref "IC14") (pin "PIN_16") (pinfunction "XI_PIN_16") (pintype "bidirectional"))
      (node (ref "XTAL2") (pin "PIN_2") (pinfunction "XC2_PIN_2") (pintype "bidirectional"))
    )
    (net (code "57") (name "Net-(IC14-XO)") (class "Default")
      (node (ref "IC14") (pin "PIN_15") (pinfunction "XO_PIN_15") (pintype "bidirectional"))
      (node (ref "XTAL2") (pin "PIN_1") (pinfunction "XC1_PIN_1") (pintype "bidirectional"))
    )
    (net (code "58") (name "Net-(M1-PIN2)") (class "Default")
      (node (ref "M1") (pin "5") (pinfunction "PIN2_5") (pintype "passive"))
      (node (ref "R20") (pin "P$1") (pinfunction "1_P$1") (pintype "passive"))
      (node (ref "R30") (pin "P$1") (pinfunction "1_P$1") (pintype "passive"))
    )
    (net (code "59") (name "Net-(M1-PIN3)") (class "Default")
      (node (ref "M1") (pin "4") (pinfunction "PIN3_4") (pintype "passive"))
      (node (ref "R21") (pin "P$1") (pinfunction "1_P$1") (pintype "passive"))
      (node (ref "R29") (pin "P$1") (pinfunction "1_P$1") (pintype "passive"))
    )
    (net (code "60") (name "Net-(R17-Pad1)") (class "Default")
      (node (ref "R17") (pin "1") (pinfunction "1_1") (pintype "passive"))
      (node (ref "U$44") (pin "PIN_2") (pinfunction "POS_PIN_2") (pintype "bidirectional"))
      (node (ref "U$44") (pin "PIN_3") (pinfunction "POS_PIN_3") (pintype "bidirectional"))
    )
    (net (code "61") (name "SYM_VCC") (class "Default")
      (node (ref "C10") (pin "2") (pinfunction "2_2") (pintype "passive"))
      (node (ref "C2") (pin "P$2") (pinfunction "2_P$2") (pintype "passive"))
      (node (ref "C3") (pin "P$1") (pinfunction "1_P$1") (pintype "passive"))
      (node (ref "C4") (pin "P$1") (pinfunction "1_P$1") (pintype "passive"))
      (node (ref "IC1") (pin "PIN_5") (pinfunction "VOUT_PIN_5") (pintype "bidirectional"))
      (node (ref "IC15") (pin "P$10") (pinfunction "VCC_P$10") (pintype "bidirectional"))
      (node (ref "IC15") (pin "P$30") (pinfunction "AVCC_P$30") (pintype "bidirectional"))
      (node (ref "IC15") (pin "P$32") (pinfunction "AREF_P$32") (pintype "bidirectional"))
      (node (ref "IC4") (pin "2") (pinfunction "S_2") (pintype "bidirectional"))
      (node (ref "IC8") (pin "2") (pinfunction "S_2") (pintype "bidirectional"))
      (node (ref "M1") (pin "6") (pinfunction "PIN1_6") (pintype "passive"))
      (node (ref "M2") (pin "PIN_2") (pinfunction "2.VCC_PIN_2") (pintype "bidirectional"))
      (node (ref "M5") (pin "3") (pinfunction "PIN4_3") (pintype "passive"))
      (node (ref "R11") (pin "P$2") (pinfunction "2_P$2") (pintype "passive"))
      (node (ref "R18") (pin "2") (pinfunction "2_2") (pintype "passive"))
      (node (ref "R19") (pin "2") (pinfunction "2_2") (pintype "passive"))
      (node (ref "R29") (pin "P$2") (pinfunction "2_P$2") (pintype "passive"))
      (node (ref "R3") (pin "P$2") (pinfunction "2_P$2") (pintype "passive"))
      (node (ref "R30") (pin "P$2") (pinfunction "2_P$2") (pintype "passive"))
      (node (ref "R4") (pin "P$2") (pinfunction "2_P$2") (pintype "passive"))
      (node (ref "R5") (pin "P$1") (pinfunction "1_P$1") (pintype "passive"))
      (node (ref "R6") (pin "P$2") (pinfunction "2_P$2") (pintype "passive"))
      (node (ref "SW1") (pin "PIN_1") (pinfunction "1_PIN_1") (pintype "passive"))
      (node (ref "SW2") (pin "PIN_1") (pinfunction "1_PIN_1") (pintype "passive"))
      (node (ref "SW3") (pin "PIN_1") (pinfunction "1_PIN_1") (pintype "passive"))
      (node (ref "SW4") (pin "PIN_1") (pinfunction "1_PIN_1") (pintype "passive"))
      (node (ref "SW5") (pin "PIN_1") (pinfunction "1_PIN_1") (pintype "passive"))
      (node (ref "TP22") (pin "1") (pinfunction "1_1") (pintype "passive"))
    )
    (net (code "62") (name "unconnected-(IC12-DRDY-PadPIN_8)") (class "Default")
      (node (ref "IC12") (pin "PIN_8") (pinfunction "DRDY_PIN_8") (pintype "bidirectional"))
    )
    (net (code "63") (name "unconnected-(IC12-INT-PadPIN_7)") (class "Default")
      (node (ref "IC12") (pin "PIN_7") (pinfunction "INT_PIN_7") (pintype "bidirectional"))
    )
    (net (code "64") (name "unconnected-(IC13-AL_L-PadPIN_6)") (class "Default")
      (node (ref "IC13") (pin "PIN_6") (pinfunction "AL_L_PIN_6") (pintype "bidirectional"))
    )
    (net (code "65") (name "unconnected-(IC13-NC-PadPIN_7)") (class "Default")
      (node (ref "IC13") (pin "PIN_7") (pinfunction "NC_PIN_7") (pintype "bidirectional"))
    )
    (net (code "66") (name "unconnected-(IC14-CLKOUT{slash}NIRQ3-PadPIN_8)") (class "Default")
      (node (ref "IC14") (pin "PIN_8") (pinfunction "CLKOUT/NIRQ3_PIN_8") (pintype "bidirectional"))
    )
    (net (code "67") (name "unconnected-(IC14-NIRQ2-PadPIN_4)") (class "Default")
      (node (ref "IC14") (pin "PIN_4") (pinfunction "NIRQ2_PIN_4") (pintype "bidirectional"))
    )
    (net (code "68") (name "unconnected-(IC15-PB2-PadP$3)") (class "Default")
      (node (ref "IC15") (pin "P$3") (pinfunction "PB2_P$3") (pintype "bidirectional"))
    )
    (net (code "69") (name "unconnected-(IC15-PB3-PadP$4)") (class "Default")
      (node (ref "IC15") (pin "P$4") (pinfunction "PB3_P$4") (pintype "bidirectional"))
    )
    (net (code "70") (name "unconnected-(IC15-PB4-PadP$5)") (class "Default")
      (node (ref "IC15") (pin "P$5") (pinfunction "PB4_P$5") (pintype "bidirectional"))
    )
    (net (code "71") (name "unconnected-(IC15-PC7-PadP$29)") (class "Default")
      (node (ref "IC15") (pin "P$29") (pinfunction "PC7_P$29") (pintype "bidirectional"))
    )
    (net (code "72") (name "unconnected-(IC15-PD6-PadP$20)") (class "Default")
      (node (ref "IC15") (pin "P$20") (pinfunction "PD6_P$20") (pintype "bidirectional"))
    )
    (net (code "73") (name "unconnected-(IC15-PD7-PadP$21)") (class "Default")
      (node (ref "IC15") (pin "P$21") (pinfunction "PD7_P$21") (pintype "bidirectional"))
    )
    (net (code "74") (name "unconnected-(M4-PIN1-Pad6)") (class "Default")
      (node (ref "M4") (pin "6") (pinfunction "PIN1_6") (pintype "passive"))
    )
    (net (code "75") (name "unconnected-(M5-PIN1-Pad6)") (class "Default")
      (node (ref "M5") (pin "6") (pinfunction "PIN1_6") (pintype "passive"))
    )
    (net (code "76") (name "unconnected-(M5-PIN5-Pad2)") (class "Default")
      (node (ref "M5") (pin "2") (pinfunction "PIN5_2") (pintype "passive"))
    )
    (net (code "77") (name "unconnected-(M7-DAT1-Pad8)") (class "Default")
      (node (ref "M7") (pin "8") (pinfunction "DAT1_8") (pintype "bidirectional"))
    )
    (net (code "78") (name "unconnected-(M7-DAT2-Pad1)") (class "Default")
      (node (ref "M7") (pin "1") (pinfunction "DAT2_1") (pintype "bidirectional"))
    )
    (net (code "79") (name "unconnected-(M7-SWA-Pad9)") (class "Default")
      (node (ref "M7") (pin "9") (pinfunction "SWA_9") (pintype "bidirectional"))
    )
    (net (code "80") (name "unconnected-(M7-SWB-Pad10)") (class "Default")
      (node (ref "M7") (pin "10") (pinfunction "SWB_10") (pintype "bidirectional"))
    )
  )
)
